# Elektroskate_Teensy_20141227.net
KiCad netlist of a schematic drawn in EAGLE
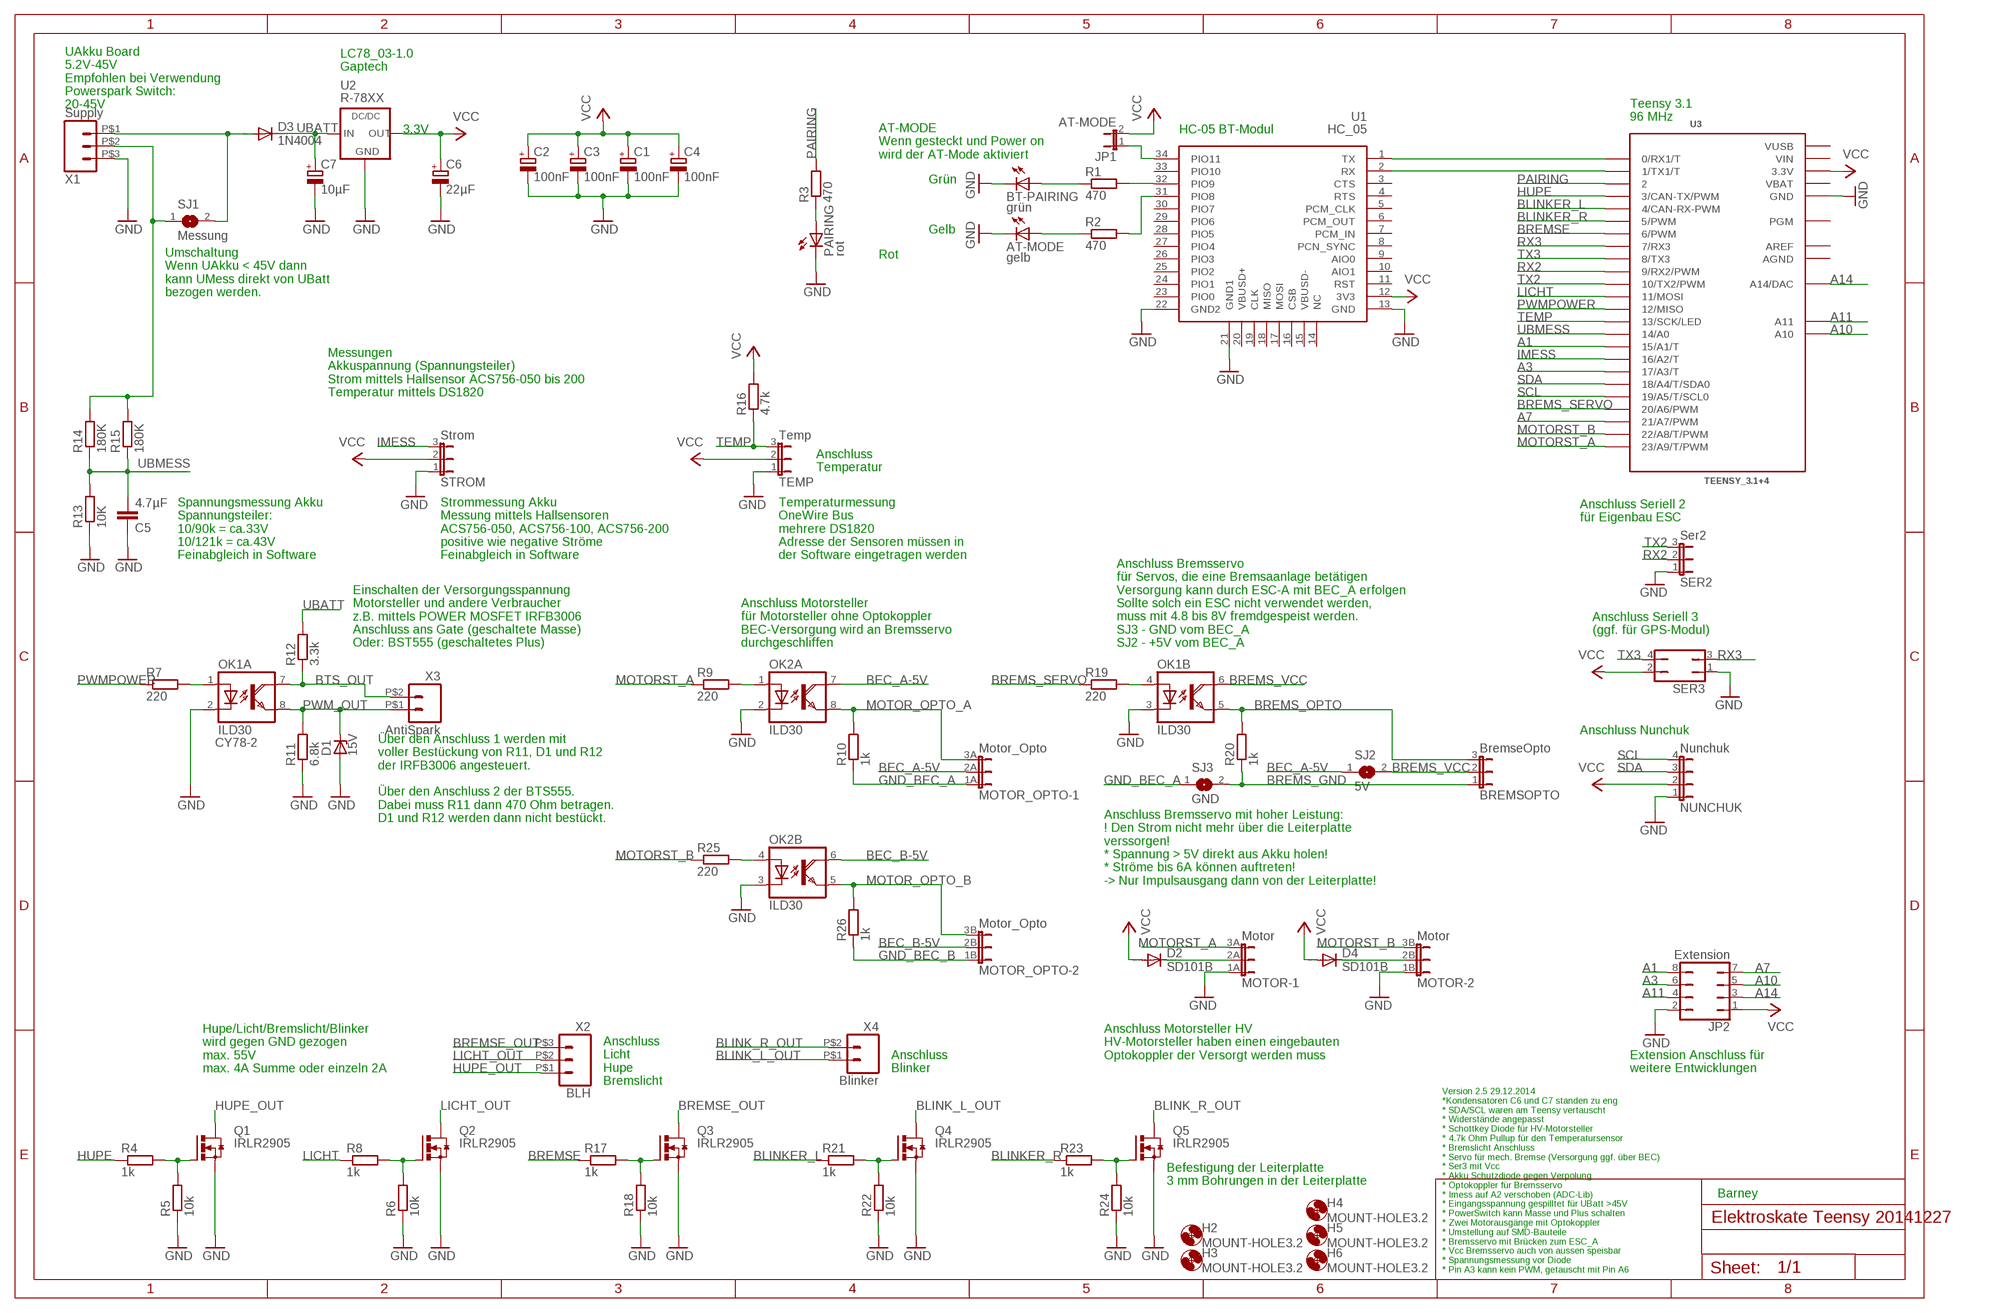
[diagram p0: schematic, sheet 1]

(export (version "E")
  (design (tool "Eeschema 10.0.6"))
  (components
    (comp (ref "AT-MODE")
      (value "gelb")
      (footprint "eagle-import:SML0805")
      (libsource (lib "eagle-import") (part "LEDSML0805"))
    )
    (comp (ref "BREMSOPTO")
      (value "BremseOpto")
      (footprint "eagle-import:JP2")
      (libsource (lib "eagle-import") (part "JP2E"))
    )
    (comp (ref "BT-PAIRING")
      (value "grün")
      (footprint "eagle-import:SML0805")
      (libsource (lib "eagle-import") (part "LEDSML0805"))
    )
    (comp (ref "C1")
      (value "100nF")
      (footprint "eagle-import:B45181A")
      (libsource (lib "eagle-import") (part "CPOL-EUB45181A"))
    )
    (comp (ref "C2")
      (value "100nF")
      (footprint "eagle-import:B45181A")
      (libsource (lib "eagle-import") (part "CPOL-EUB45181A"))
    )
    (comp (ref "C3")
      (value "100nF")
      (footprint "eagle-import:B45181A")
      (libsource (lib "eagle-import") (part "CPOL-EUB45181A"))
    )
    (comp (ref "C4")
      (value "100nF")
      (footprint "eagle-import:B45181A")
      (libsource (lib "eagle-import") (part "CPOL-EUB45181A"))
    )
    (comp (ref "C5")
      (value "4.7µF")
      (footprint "eagle-import:C1206")
      (libsource (lib "eagle-import") (part "C-EUC1206"))
    )
    (comp (ref "C6")
      (value "22µF")
      (footprint "eagle-import:UD-4X5,8_NICHICON")
      (libsource (lib "eagle-import") (part "CPOL-EUUD-4X5,8"))
    )
    (comp (ref "C7")
      (value "10µF")
      (footprint "eagle-import:UD-6,3X5,8_NICHICON")
      (libsource (lib "eagle-import") (part "CPOL-EUUD-6,3X8,8"))
    )
    (comp (ref "D1")
      (value "15V")
      (footprint "eagle-import:DO35Z10")
      (libsource (lib "eagle-import") (part "ZPD"))
    )
    (comp (ref "D2")
      (value "SD101B")
      (footprint "eagle-import:SOD123")
      (libsource (lib "eagle-import") (part "MBR0520LT"))
    )
    (comp (ref "D3")
      (value "1N4004")
      (footprint "eagle-import:DO41-10")
      (libsource (lib "eagle-import") (part "1N4004"))
    )
    (comp (ref "D4")
      (value "SD101B")
      (footprint "eagle-import:SOD123")
      (libsource (lib "eagle-import") (part "MBR0520LT"))
    )
    (comp (ref "H2")
      (value "MOUNT-HOLE3.2")
      (footprint "eagle-import:3,2")
      (libsource (lib "eagle-import") (part "MOUNT-HOLE3.2"))
    )
    (comp (ref "H3")
      (value "MOUNT-HOLE3.2")
      (footprint "eagle-import:3,2")
      (libsource (lib "eagle-import") (part "MOUNT-HOLE3.2"))
    )
    (comp (ref "H4")
      (value "MOUNT-HOLE3.2")
      (footprint "eagle-import:3,2")
      (libsource (lib "eagle-import") (part "MOUNT-HOLE3.2"))
    )
    (comp (ref "H5")
      (value "MOUNT-HOLE3.2")
      (footprint "eagle-import:3,2")
      (libsource (lib "eagle-import") (part "MOUNT-HOLE3.2"))
    )
    (comp (ref "H6")
      (value "MOUNT-HOLE3.2")
      (footprint "eagle-import:3,2")
      (libsource (lib "eagle-import") (part "MOUNT-HOLE3.2"))
    )
    (comp (ref "JP1")
      (value "AT-MODE")
      (footprint "eagle-import:JP1")
      (libsource (lib "eagle-import") (part "JP1E"))
    )
    (comp (ref "JP2")
      (value "Extension")
      (footprint "eagle-import:JP4Q")
      (libsource (lib "eagle-import") (part "JP4Q"))
    )
    (comp (ref "MOTOR")
      (value "Motor")
      (footprint "eagle-import:JP3Q")
      (libsource (lib "eagle-import") (part "JP3QE"))
    )
    (comp (ref "MOTOR_OPTO")
      (value "Motor_Opto")
      (footprint "eagle-import:JP3Q")
      (libsource (lib "eagle-import") (part "JP3QE"))
    )
    (comp (ref "NUNCHUK")
      (value "Nunchuk")
      (footprint "eagle-import:JP4")
      (libsource (lib "eagle-import") (part "JP4E"))
    )
    (comp (ref "OK1")
      (value "ILD30")
      (footprint "eagle-import:DIL08")
      (fields (field (name "MF") "VISHAY/TELEFUNKEN"))
      (libsource (lib "eagle-import") (part "ILD30"))
    )
    (comp (ref "OK2")
      (value "ILD30")
      (footprint "eagle-import:DIL08")
      (fields (field (name "MF") "VISHAY/TELEFUNKEN"))
      (libsource (lib "eagle-import") (part "ILD30"))
    )
    (comp (ref "PAIRING")
      (value "rot")
      (footprint "eagle-import:SML0805")
      (libsource (lib "eagle-import") (part "LEDSML0805"))
    )
    (comp (ref "Q1")
      (value "IRLR2905")
      (footprint "eagle-import:D-PAK_TO252AA")
      (libsource (lib "eagle-import") (part "IRLR2905"))
    )
    (comp (ref "Q2")
      (value "IRLR2905")
      (footprint "eagle-import:D-PAK_TO252AA")
      (libsource (lib "eagle-import") (part "IRLR2905"))
    )
    (comp (ref "Q3")
      (value "IRLR2905")
      (footprint "eagle-import:D-PAK_TO252AA")
      (libsource (lib "eagle-import") (part "IRLR2905"))
    )
    (comp (ref "Q4")
      (value "IRLR2905")
      (footprint "eagle-import:D-PAK_TO252AA")
      (libsource (lib "eagle-import") (part "IRLR2905"))
    )
    (comp (ref "Q5")
      (value "IRLR2905")
      (footprint "eagle-import:D-PAK_TO252AA")
      (libsource (lib "eagle-import") (part "IRLR2905"))
    )
    (comp (ref "R1")
      (value "470")
      (footprint "eagle-import:R1206")
      (libsource (lib "eagle-import") (part "R-EU_R1206"))
    )
    (comp (ref "R2")
      (value "470")
      (footprint "eagle-import:R1206")
      (libsource (lib "eagle-import") (part "R-EU_R1206"))
    )
    (comp (ref "R3")
      (value "470")
      (footprint "eagle-import:R1206")
      (libsource (lib "eagle-import") (part "R-EU_R1206"))
    )
    (comp (ref "R4")
      (value "1k")
      (footprint "eagle-import:R1206")
      (libsource (lib "eagle-import") (part "R-EU_R1206"))
    )
    (comp (ref "R5")
      (value "10k")
      (footprint "eagle-import:R1206")
      (libsource (lib "eagle-import") (part "R-EU_R1206"))
    )
    (comp (ref "R6")
      (value "10k")
      (footprint "eagle-import:R1206")
      (libsource (lib "eagle-import") (part "R-EU_R1206"))
    )
    (comp (ref "R7")
      (value "220")
      (footprint "eagle-import:R1206")
      (libsource (lib "eagle-import") (part "R-EU_R1206"))
    )
    (comp (ref "R8")
      (value "1k")
      (footprint "eagle-import:R1206")
      (libsource (lib "eagle-import") (part "R-EU_R1206"))
    )
    (comp (ref "R9")
      (value "220")
      (footprint "eagle-import:R1206")
      (libsource (lib "eagle-import") (part "R-EU_R1206"))
    )
    (comp (ref "R10")
      (value "1k")
      (footprint "eagle-import:R1206")
      (libsource (lib "eagle-import") (part "R-EU_R1206"))
    )
    (comp (ref "R11")
      (value "6.8k")
      (footprint "eagle-import:R1206")
      (libsource (lib "eagle-import") (part "R-EU_R1206"))
    )
    (comp (ref "R12")
      (value "3.3k")
      (footprint "eagle-import:R1206")
      (libsource (lib "eagle-import") (part "R-EU_R1206"))
    )
    (comp (ref "R13")
      (value "10K")
      (footprint "eagle-import:R1206")
      (libsource (lib "eagle-import") (part "R-EU_R1206"))
    )
    (comp (ref "R14")
      (value "180K")
      (footprint "eagle-import:R1206")
      (libsource (lib "eagle-import") (part "R-EU_R1206"))
    )
    (comp (ref "R15")
      (value "180K")
      (footprint "eagle-import:R1206")
      (libsource (lib "eagle-import") (part "R-EU_R1206"))
    )
    (comp (ref "R16")
      (value "4.7k")
      (footprint "eagle-import:R1206")
      (libsource (lib "eagle-import") (part "R-EU_R1206"))
    )
    (comp (ref "R17")
      (value "1k")
      (footprint "eagle-import:R1206")
      (libsource (lib "eagle-import") (part "R-EU_R1206"))
    )
    (comp (ref "R18")
      (value "10k")
      (footprint "eagle-import:R1206")
      (libsource (lib "eagle-import") (part "R-EU_R1206"))
    )
    (comp (ref "R19")
      (value "220")
      (footprint "eagle-import:R1206")
      (libsource (lib "eagle-import") (part "R-EU_R1206"))
    )
    (comp (ref "R20")
      (value "1k")
      (footprint "eagle-import:R1206")
      (libsource (lib "eagle-import") (part "R-EU_R1206"))
    )
    (comp (ref "R21")
      (value "1k")
      (footprint "eagle-import:R1206")
      (libsource (lib "eagle-import") (part "R-EU_R1206"))
    )
    (comp (ref "R22")
      (value "10k")
      (footprint "eagle-import:R1206")
      (libsource (lib "eagle-import") (part "R-EU_R1206"))
    )
    (comp (ref "R23")
      (value "1k")
      (footprint "eagle-import:R1206")
      (libsource (lib "eagle-import") (part "R-EU_R1206"))
    )
    (comp (ref "R24")
      (value "10k")
      (footprint "eagle-import:R1206")
      (libsource (lib "eagle-import") (part "R-EU_R1206"))
    )
    (comp (ref "R25")
      (value "220")
      (footprint "eagle-import:R1206")
      (libsource (lib "eagle-import") (part "R-EU_R1206"))
    )
    (comp (ref "R26")
      (value "1k")
      (footprint "eagle-import:R1206")
      (libsource (lib "eagle-import") (part "R-EU_R1206"))
    )
    (comp (ref "SER2")
      (value "Ser2")
      (footprint "eagle-import:JP2")
      (libsource (lib "eagle-import") (part "JP2E"))
    )
    (comp (ref "SER3")
      (value "JP2Q")
      (footprint "eagle-import:JP2Q")
      (libsource (lib "eagle-import") (part "JP2Q"))
    )
    (comp (ref "SJ1")
      (value "Messung")
      (footprint "eagle-import:SJ")
      (libsource (lib "eagle-import") (part "SJ"))
    )
    (comp (ref "SJ2") (value "5V") (footprint "eagle-import:SJ") (libsource (lib "eagle-import") (part "SJ")))
    (comp (ref "SJ3")
      (value "GND")
      (footprint "eagle-import:SJ")
      (libsource (lib "eagle-import") (part "SJ"))
    )
    (comp (ref "STROM")
      (value "Strom")
      (footprint "eagle-import:JP2")
      (libsource (lib "eagle-import") (part "JP2E"))
    )
    (comp (ref "TEMP")
      (value "Temp")
      (footprint "eagle-import:JP2")
      (libsource (lib "eagle-import") (part "JP2E"))
    )
    (comp (ref "U1")
      (value "HC_05")
      (footprint "eagle-import:BLUETOOTH_SMD")
      (libsource (lib "eagle-import") (part "HC_05"))
    )
    (comp (ref "U2")
      (value "R-78XX")
      (footprint "eagle-import:R-78XX")
      (fields (field (name "SPANNUNG") "3.3V"))
      (libsource (lib "eagle-import") (part "R-78XX"))
    )
    (comp (ref "U3")
      (value "TEENSY_3.1+4")
      (footprint "eagle-import:TEENSY_3.1+4")
      (libsource (lib "eagle-import") (part "TEENSY_3.1+4"))
    )
    (comp (ref "X1")
      (value "Supply")
      (footprint "eagle-import:03W")
      (libsource (lib "eagle-import") (part "PSS254_3GEWINKELT"))
    )
    (comp (ref "X2")
      (value "BLH")
      (footprint "eagle-import:03W")
      (libsource (lib "eagle-import") (part "PSS254_3GEWINKELT"))
    )
    (comp (ref "X3")
      (value "AntiSpark")
      (footprint "eagle-import:02W")
      (libsource (lib "eagle-import") (part "PSS254_2GEWINKELT"))
    )
    (comp (ref "X4")
      (value "Blinker")
      (footprint "eagle-import:02W")
      (libsource (lib "eagle-import") (part "PSS254_2GEWINKELT"))
    )
  )
  (nets
    (net (code "1") (name "/A1") (class "Default")
      (node (ref "JP2") (pin "8") (pinfunction "8_8") (pintype "passive"))
      (node (ref "U3") (pin "15/A1") (pinfunction "15/A1/T_15/A1") (pintype "bidirectional"))
    )
    (net (code "2") (name "/A3") (class "Default")
      (node (ref "JP2") (pin "6") (pinfunction "6_6") (pintype "passive"))
      (node (ref "U3") (pin "17/A3") (pinfunction "17/A3/T_17/A3") (pintype "bidirectional"))
    )
    (net (code "3") (name "/A7") (class "Default")
      (node (ref "JP2") (pin "7") (pinfunction "7_7") (pintype "passive"))
      (node (ref "U3") (pin "21/A7") (pinfunction "21/A7/PWM_21/A7") (pintype "bidirectional"))
    )
    (net (code "4") (name "/A10") (class "Default")
      (node (ref "JP2") (pin "5") (pinfunction "5_5") (pintype "passive"))
      (node (ref "U3") (pin "A10") (pinfunction "A10_A10") (pintype "bidirectional"))
    )
    (net (code "5") (name "/A11") (class "Default")
      (node (ref "JP2") (pin "4") (pinfunction "4_4") (pintype "passive"))
      (node (ref "U3") (pin "A11") (pinfunction "A11_A11") (pintype "bidirectional"))
    )
    (net (code "6") (name "/A14") (class "Default")
      (node (ref "JP2") (pin "3") (pinfunction "3_3") (pintype "passive"))
      (node (ref "U3") (pin "A14") (pinfunction "A14/DAC_A14") (pintype "bidirectional"))
    )
    (net (code "7") (name "/AGND") (class "Default")
      (node (ref "U3") (pin "AGND") (pinfunction "AGND_AGND") (pintype "power_in"))
    )
    (net (code "8") (name "/AREF") (class "Default")
      (node (ref "U3") (pin "AREF") (pinfunction "AREF_AREF") (pintype "power_in"))
    )
    (net (code "9") (name "/BEC_A-5V") (class "Default")
      (node (ref "MOTOR_OPTO") (pin "2A") (pinfunction "2_2A") (pintype "passive"))
      (node (ref "OK2") (pin "7") (pinfunction "COL_7") (pintype "passive"))
      (node (ref "SJ2") (pin "1") (pinfunction "1_1") (pintype "passive"))
    )
    (net (code "10") (name "/BEC_B-5V") (class "Default")
      (node (ref "MOTOR_OPTO") (pin "2B") (pinfunction "2_2B") (pintype "passive"))
      (node (ref "OK2") (pin "6") (pinfunction "COL_6") (pintype "passive"))
    )
    (net (code "11") (name "/BLINKER_L") (class "Default")
      (node (ref "R21") (pin "1") (pinfunction "1_1") (pintype "passive"))
      (node (ref "U3") (pin "4") (pinfunction "4/CAN-RX-PWM_4") (pintype "bidirectional"))
    )
    (net (code "12") (name "/BLINKER_R") (class "Default")
      (node (ref "R23") (pin "1") (pinfunction "1_1") (pintype "passive"))
      (node (ref "U3") (pin "5") (pinfunction "5/PWM_5") (pintype "bidirectional"))
    )
    (net (code "13") (name "/BLINK_L_OUT") (class "Default")
      (node (ref "Q4") (pin "4") (pinfunction "D_4") (pintype "passive"))
      (node (ref "X4") (pin "P$1") (pinfunction "1_P$1") (pintype "passive"))
    )
    (net (code "14") (name "/BLINK_R_OUT") (class "Default")
      (node (ref "Q5") (pin "4") (pinfunction "D_4") (pintype "passive"))
      (node (ref "X4") (pin "P$2") (pinfunction "2_P$2") (pintype "passive"))
    )
    (net (code "15") (name "/BREMSE") (class "Default")
      (node (ref "R17") (pin "1") (pinfunction "1_1") (pintype "passive"))
      (node (ref "U3") (pin "6") (pinfunction "6/PWM_6") (pintype "bidirectional"))
    )
    (net (code "16") (name "/BREMSE_OUT") (class "Default")
      (node (ref "Q3") (pin "4") (pinfunction "D_4") (pintype "passive"))
      (node (ref "X2") (pin "P$3") (pinfunction "3_P$3") (pintype "passive"))
    )
    (net (code "17") (name "/BREMS_GND") (class "Default")
      (node (ref "BREMSOPTO") (pin "1") (pinfunction "1_1") (pintype "passive"))
      (node (ref "R20") (pin "1") (pinfunction "1_1") (pintype "passive"))
      (node (ref "SJ3") (pin "2") (pinfunction "2_2") (pintype "passive"))
    )
    (net (code "18") (name "/BREMS_OPTO") (class "Default")
      (node (ref "BREMSOPTO") (pin "3") (pinfunction "3_3") (pintype "passive"))
      (node (ref "OK1") (pin "5") (pinfunction "EMI_5") (pintype "passive"))
      (node (ref "R20") (pin "2") (pinfunction "2_2") (pintype "passive"))
    )
    (net (code "19") (name "/BREMS_SERVO") (class "Default")
      (node (ref "R19") (pin "1") (pinfunction "1_1") (pintype "passive"))
      (node (ref "U3") (pin "20/A6") (pinfunction "20/A6/PWM_20/A6") (pintype "bidirectional"))
    )
    (net (code "20") (name "/BREMS_VCC") (class "Default")
      (node (ref "BREMSOPTO") (pin "2") (pinfunction "2_2") (pintype "passive"))
      (node (ref "OK1") (pin "6") (pinfunction "COL_6") (pintype "passive"))
      (node (ref "SJ2") (pin "2") (pinfunction "2_2") (pintype "passive"))
    )
    (net (code "21") (name "/BTS_OUT") (class "Default")
      (node (ref "OK1") (pin "7") (pinfunction "COL_7") (pintype "passive"))
      (node (ref "R12") (pin "1") (pinfunction "1_1") (pintype "passive"))
      (node (ref "X3") (pin "P$2") (pinfunction "2_P$2") (pintype "passive"))
    )
    (net (code "22") (name "/GND_BEC_A") (class "Default")
      (node (ref "MOTOR_OPTO") (pin "1A") (pinfunction "1_1A") (pintype "passive"))
      (node (ref "R10") (pin "1") (pinfunction "1_1") (pintype "passive"))
      (node (ref "SJ3") (pin "1") (pinfunction "1_1") (pintype "passive"))
    )
    (net (code "23") (name "/GND_BEC_B") (class "Default")
      (node (ref "MOTOR_OPTO") (pin "1B") (pinfunction "1_1B") (pintype "passive"))
      (node (ref "R26") (pin "1") (pinfunction "1_1") (pintype "passive"))
    )
    (net (code "24") (name "/HUPE") (class "Default")
      (node (ref "R4") (pin "1") (pinfunction "1_1") (pintype "passive"))
      (node (ref "U3") (pin "3") (pinfunction "3/CAN-TX/PWM_3") (pintype "bidirectional"))
    )
    (net (code "25") (name "/HUPE_OUT") (class "Default")
      (node (ref "Q1") (pin "4") (pinfunction "D_4") (pintype "passive"))
      (node (ref "X2") (pin "P$1") (pinfunction "1_P$1") (pintype "passive"))
    )
    (net (code "26") (name "/IMESS") (class "Default")
      (node (ref "STROM") (pin "3") (pinfunction "3_3") (pintype "passive"))
      (node (ref "U3") (pin "16/A2") (pinfunction "16/A2/T_16/A2") (pintype "bidirectional"))
    )
    (net (code "27") (name "/LICHT") (class "Default")
      (node (ref "R8") (pin "1") (pinfunction "1_1") (pintype "passive"))
      (node (ref "U3") (pin "11") (pinfunction "11/MOSI_11") (pintype "bidirectional"))
    )
    (net (code "28") (name "/LICHT_OUT") (class "Default")
      (node (ref "Q2") (pin "4") (pinfunction "D_4") (pintype "passive"))
      (node (ref "X2") (pin "P$2") (pinfunction "2_P$2") (pintype "passive"))
    )
    (net (code "29") (name "/MOTORST_A") (class "Default")
      (node (ref "MOTOR") (pin "3A") (pinfunction "3_3A") (pintype "passive"))
      (node (ref "R9") (pin "1") (pinfunction "1_1") (pintype "passive"))
      (node (ref "U3") (pin "23/A9") (pinfunction "23/A9/T/PWM_23/A9") (pintype "bidirectional"))
    )
    (net (code "30") (name "/MOTORST_B") (class "Default")
      (node (ref "MOTOR") (pin "3B") (pinfunction "3_3B") (pintype "passive"))
      (node (ref "R25") (pin "1") (pinfunction "1_1") (pintype "passive"))
      (node (ref "U3") (pin "22/A8") (pinfunction "22/A8/T/PWM_22/A8") (pintype "bidirectional"))
    )
    (net (code "31") (name "/MOTOR_OPTO_A") (class "Default")
      (node (ref "MOTOR_OPTO") (pin "3A") (pinfunction "3_3A") (pintype "passive"))
      (node (ref "OK2") (pin "8") (pinfunction "EMI_8") (pintype "passive"))
      (node (ref "R10") (pin "2") (pinfunction "2_2") (pintype "passive"))
    )
    (net (code "32") (name "/MOTOR_OPTO_B") (class "Default")
      (node (ref "MOTOR_OPTO") (pin "3B") (pinfunction "3_3B") (pintype "passive"))
      (node (ref "OK2") (pin "5") (pinfunction "EMI_5") (pintype "passive"))
      (node (ref "R26") (pin "2") (pinfunction "2_2") (pintype "passive"))
    )
    (net (code "33") (name "/PAIRING") (class "Default")
      (node (ref "R3") (pin "2") (pinfunction "2_2") (pintype "passive"))
      (node (ref "U3") (pin "2") (pinfunction "2_2") (pintype "bidirectional"))
    )
    (net (code "34") (name "/PWMPOWER") (class "Default")
      (node (ref "R7") (pin "1") (pinfunction "1_1") (pintype "passive"))
      (node (ref "U3") (pin "12") (pinfunction "12/MISO_12") (pintype "bidirectional"))
    )
    (net (code "35") (name "/PWM_OUT") (class "Default")
      (node (ref "D1") (pin "C") (pinfunction "C_C") (pintype "passive"))
      (node (ref "OK1") (pin "8") (pinfunction "EMI_8") (pintype "passive"))
      (node (ref "R11") (pin "2") (pinfunction "2_2") (pintype "passive"))
      (node (ref "X3") (pin "P$1") (pinfunction "1_P$1") (pintype "passive"))
    )
    (net (code "36") (name "/RX2") (class "Default")
      (node (ref "SER2") (pin "2") (pinfunction "2_2") (pintype "passive"))
      (node (ref "U3") (pin "9") (pinfunction "9/RX2/PWM_9") (pintype "bidirectional"))
    )
    (net (code "37") (name "/RX3") (class "Default")
      (node (ref "SER3") (pin "3") (pinfunction "3_3") (pintype "passive"))
      (node (ref "U3") (pin "7") (pinfunction "7/RX3_7") (pintype "bidirectional"))
    )
    (net (code "38") (name "/SCL") (class "Default")
      (node (ref "NUNCHUK") (pin "4") (pinfunction "4_4") (pintype "passive"))
      (node (ref "U3") (pin "19/A5") (pinfunction "19/A5/T/SCL0_19/A5") (pintype "bidirectional"))
    )
    (net (code "39") (name "/SDA") (class "Default")
      (node (ref "NUNCHUK") (pin "3") (pinfunction "3_3") (pintype "passive"))
      (node (ref "U3") (pin "18/A4") (pinfunction "18/A4/T/SDA0_18/A4") (pintype "bidirectional"))
    )
    (net (code "40") (name "/TEMP") (class "Default")
      (node (ref "R16") (pin "1") (pinfunction "1_1") (pintype "passive"))
      (node (ref "TEMP") (pin "3") (pinfunction "3_3") (pintype "passive"))
      (node (ref "U3") (pin "13") (pinfunction "13/SCK/LED_13") (pintype "bidirectional"))
    )
    (net (code "41") (name "/TX2") (class "Default")
      (node (ref "SER2") (pin "3") (pinfunction "3_3") (pintype "passive"))
      (node (ref "U3") (pin "10") (pinfunction "10/TX2/PWM_10") (pintype "bidirectional"))
    )
    (net (code "42") (name "/TX3") (class "Default")
      (node (ref "SER3") (pin "4") (pinfunction "4_4") (pintype "passive"))
      (node (ref "U3") (pin "8") (pinfunction "8/TX3_8") (pintype "bidirectional"))
    )
    (net (code "43") (name "/UBATT") (class "Default")
      (node (ref "C7") (pin "+") (pinfunction "+_+") (pintype "passive"))
      (node (ref "D3") (pin "C") (pinfunction "C_C") (pintype "passive"))
      (node (ref "R12") (pin "2") (pinfunction "2_2") (pintype "passive"))
      (node (ref "U2") (pin "1") (pinfunction "IN_1") (pintype "input"))
    )
    (net (code "44") (name "/UBMESS") (class "Default")
      (node (ref "C5") (pin "2") (pinfunction "2_2") (pintype "passive"))
      (node (ref "R13") (pin "2") (pinfunction "2_2") (pintype "passive"))
      (node (ref "R14") (pin "1") (pinfunction "1_1") (pintype "passive"))
      (node (ref "R15") (pin "1") (pinfunction "1_1") (pintype "passive"))
      (node (ref "U3") (pin "14/A0") (pinfunction "14/A0_14/A0") (pintype "bidirectional"))
    )
    (net (code "45") (name "/VBAT") (class "Default")
      (node (ref "U3") (pin "VBAT") (pinfunction "VBAT_VBAT") (pintype "power_in"))
    )
    (net (code "46") (name "/VIN") (class "Default")
      (node (ref "U3") (pin "VIN") (pinfunction "VIN_VIN") (pintype "power_in"))
    )
    (net (code "47") (name "/VUSB") (class "Default")
      (node (ref "U3") (pin "VUSB") (pinfunction "VUSB_VUSB") (pintype "power_in"))
    )
    (net (code "48") (name "GND") (class "Default")
      (node (ref "AT-MODE") (pin "C") (pinfunction "C_C") (pintype "passive"))
      (node (ref "BT-PAIRING") (pin "C") (pinfunction "C_C") (pintype "passive"))
      (node (ref "C1") (pin "-") (pinfunction "-_-") (pintype "passive"))
      (node (ref "C2") (pin "-") (pinfunction "-_-") (pintype "passive"))
      (node (ref "C3") (pin "-") (pinfunction "-_-") (pintype "passive"))
      (node (ref "C4") (pin "-") (pinfunction "-_-") (pintype "passive"))
      (node (ref "C5") (pin "1") (pinfunction "1_1") (pintype "passive"))
      (node (ref "C6") (pin "-") (pinfunction "-_-") (pintype "passive"))
      (node (ref "C7") (pin "-") (pinfunction "-_-") (pintype "passive"))
      (node (ref "D1") (pin "A") (pinfunction "A_A") (pintype "passive"))
      (node (ref "JP2") (pin "2") (pinfunction "2_2") (pintype "passive"))
      (node (ref "MOTOR") (pin "1A") (pinfunction "1_1A") (pintype "passive"))
      (node (ref "MOTOR") (pin "1B") (pinfunction "1_1B") (pintype "passive"))
      (node (ref "NUNCHUK") (pin "1") (pinfunction "1_1") (pintype "passive"))
      (node (ref "OK1") (pin "2") (pinfunction "C_2") (pintype "passive"))
      (node (ref "OK1") (pin "3") (pinfunction "C_3") (pintype "passive"))
      (node (ref "OK2") (pin "2") (pinfunction "C_2") (pintype "passive"))
      (node (ref "OK2") (pin "3") (pinfunction "C_3") (pintype "passive"))
      (node (ref "PAIRING") (pin "C") (pinfunction "C_C") (pintype "passive"))
      (node (ref "Q1") (pin "3") (pinfunction "S_3") (pintype "passive"))
      (node (ref "Q2") (pin "3") (pinfunction "S_3") (pintype "passive"))
      (node (ref "Q3") (pin "3") (pinfunction "S_3") (pintype "passive"))
      (node (ref "Q4") (pin "3") (pinfunction "S_3") (pintype "passive"))
      (node (ref "Q5") (pin "3") (pinfunction "S_3") (pintype "passive"))
      (node (ref "R11") (pin "1") (pinfunction "1_1") (pintype "passive"))
      (node (ref "R13") (pin "1") (pinfunction "1_1") (pintype "passive"))
      (node (ref "R18") (pin "1") (pinfunction "1_1") (pintype "passive"))
      (node (ref "R22") (pin "1") (pinfunction "1_1") (pintype "passive"))
      (node (ref "R24") (pin "1") (pinfunction "1_1") (pintype "passive"))
      (node (ref "R5") (pin "1") (pinfunction "1_1") (pintype "passive"))
      (node (ref "R6") (pin "1") (pinfunction "1_1") (pintype "passive"))
      (node (ref "SER2") (pin "1") (pinfunction "1_1") (pintype "passive"))
      (node (ref "SER3") (pin "1") (pinfunction "1_1") (pintype "passive"))
      (node (ref "STROM") (pin "1") (pinfunction "1_1") (pintype "passive"))
      (node (ref "TEMP") (pin "1") (pinfunction "1_1") (pintype "passive"))
      (node (ref "U1") (pin "13") (pinfunction "GND_13") (pintype "bidirectional"))
      (node (ref "U1") (pin "21") (pinfunction "GND1_21") (pintype "bidirectional"))
      (node (ref "U1") (pin "22") (pinfunction "GND2_22") (pintype "bidirectional"))
      (node (ref "U2") (pin "2") (pinfunction "GND_2") (pintype "input"))
      (node (ref "U3") (pin "GND") (pinfunction "GND_GND") (pintype "power_in"))
      (node (ref "U3") (pin "GND1") (pinfunction "GND_GND1") (pintype "power_in"))
      (node (ref "X1") (pin "P$3") (pinfunction "3_P$3") (pintype "passive"))
    )
    (net (code "49") (name "Net-(AT-MODE-PadA)") (class "Default")
      (node (ref "AT-MODE") (pin "A") (pinfunction "A_A") (pintype "passive"))
      (node (ref "R2") (pin "1") (pinfunction "1_1") (pintype "passive"))
    )
    (net (code "50") (name "Net-(BT-PAIRING-PadA)") (class "Default")
      (node (ref "BT-PAIRING") (pin "A") (pinfunction "A_A") (pintype "passive"))
      (node (ref "R1") (pin "1") (pinfunction "1_1") (pintype "passive"))
    )
    (net (code "51") (name "Net-(MOTORA-2)") (class "Default")
      (node (ref "D2") (pin "C") (pinfunction "C_C") (pintype "passive"))
      (node (ref "MOTOR") (pin "2A") (pinfunction "2_2A") (pintype "passive"))
    )
    (net (code "52") (name "Net-(MOTORB-2)") (class "Default")
      (node (ref "D4") (pin "C") (pinfunction "C_C") (pintype "passive"))
      (node (ref "MOTOR") (pin "2B") (pinfunction "2_2B") (pintype "passive"))
    )
    (net (code "53") (name "Net-(OK1A-A)") (class "Default")
      (node (ref "OK1") (pin "1") (pinfunction "A_1") (pintype "passive"))
      (node (ref "R7") (pin "2") (pinfunction "2_2") (pintype "passive"))
    )
    (net (code "54") (name "Net-(OK1B-A)") (class "Default")
      (node (ref "OK1") (pin "4") (pinfunction "A_4") (pintype "passive"))
      (node (ref "R19") (pin "2") (pinfunction "2_2") (pintype "passive"))
    )
    (net (code "55") (name "Net-(OK2A-A)") (class "Default")
      (node (ref "OK2") (pin "1") (pinfunction "A_1") (pintype "passive"))
      (node (ref "R9") (pin "2") (pinfunction "2_2") (pintype "passive"))
    )
    (net (code "56") (name "Net-(OK2B-A)") (class "Default")
      (node (ref "OK2") (pin "4") (pinfunction "A_4") (pintype "passive"))
      (node (ref "R25") (pin "2") (pinfunction "2_2") (pintype "passive"))
    )
    (net (code "57") (name "Net-(PAIRING-PadA)") (class "Default")
      (node (ref "PAIRING") (pin "A") (pinfunction "A_A") (pintype "passive"))
      (node (ref "R3") (pin "1") (pinfunction "1_1") (pintype "passive"))
    )
    (net (code "58") (name "Net-(Q1-G)") (class "Default")
      (node (ref "Q1") (pin "1") (pinfunction "G_1") (pintype "passive"))
      (node (ref "R4") (pin "2") (pinfunction "2_2") (pintype "passive"))
      (node (ref "R5") (pin "2") (pinfunction "2_2") (pintype "passive"))
    )
    (net (code "59") (name "Net-(Q2-G)") (class "Default")
      (node (ref "Q2") (pin "1") (pinfunction "G_1") (pintype "passive"))
      (node (ref "R6") (pin "2") (pinfunction "2_2") (pintype "passive"))
      (node (ref "R8") (pin "2") (pinfunction "2_2") (pintype "passive"))
    )
    (net (code "60") (name "Net-(Q3-G)") (class "Default")
      (node (ref "Q3") (pin "1") (pinfunction "G_1") (pintype "passive"))
      (node (ref "R17") (pin "2") (pinfunction "2_2") (pintype "passive"))
      (node (ref "R18") (pin "2") (pinfunction "2_2") (pintype "passive"))
    )
    (net (code "61") (name "Net-(Q4-G)") (class "Default")
      (node (ref "Q4") (pin "1") (pinfunction "G_1") (pintype "passive"))
      (node (ref "R21") (pin "2") (pinfunction "2_2") (pintype "passive"))
      (node (ref "R22") (pin "2") (pinfunction "2_2") (pintype "passive"))
    )
    (net (code "62") (name "Net-(Q5-G)") (class "Default")
      (node (ref "Q5") (pin "1") (pinfunction "G_1") (pintype "passive"))
      (node (ref "R23") (pin "2") (pinfunction "2_2") (pintype "passive"))
      (node (ref "R24") (pin "2") (pinfunction "2_2") (pintype "passive"))
    )
    (net (code "63") (name "Net-(U1-PIO8)") (class "Default")
      (node (ref "R2") (pin "2") (pinfunction "2_2") (pintype "passive"))
      (node (ref "U1") (pin "31") (pinfunction "PIO8_31") (pintype "bidirectional"))
    )
    (net (code "64") (name "Net-(U1-PIO9)") (class "Default")
      (node (ref "R1") (pin "2") (pinfunction "2_2") (pintype "passive"))
      (node (ref "U1") (pin "32") (pinfunction "PIO9_32") (pintype "bidirectional"))
    )
    (net (code "65") (name "Net-(U1-PIO11)") (class "Default")
      (node (ref "JP1") (pin "1") (pinfunction "1_1") (pintype "passive"))
      (node (ref "U1") (pin "34") (pinfunction "PIO11_34") (pintype "bidirectional"))
    )
    (net (code "66") (name "Net-(U1-RX)") (class "Default")
      (node (ref "U1") (pin "2") (pinfunction "RX_2") (pintype "bidirectional"))
      (node (ref "U3") (pin "1") (pinfunction "1/TX1/T_1") (pintype "bidirectional"))
    )
    (net (code "67") (name "Net-(U1-TX)") (class "Default")
      (node (ref "U1") (pin "1") (pinfunction "TX_1") (pintype "bidirectional"))
      (node (ref "U3") (pin "0") (pinfunction "0/RX1/T_0") (pintype "bidirectional"))
    )
    (net (code "68") (name "Net-(X1-1)") (class "Default")
      (node (ref "D3") (pin "A") (pinfunction "A_A") (pintype "passive"))
      (node (ref "SJ1") (pin "2") (pinfunction "2_2") (pintype "passive"))
      (node (ref "X1") (pin "P$1") (pinfunction "1_P$1") (pintype "passive"))
    )
    (net (code "69") (name "Net-(X1-2)") (class "Default")
      (node (ref "R14") (pin "2") (pinfunction "2_2") (pintype "passive"))
      (node (ref "R15") (pin "2") (pinfunction "2_2") (pintype "passive"))
      (node (ref "SJ1") (pin "1") (pinfunction "1_1") (pintype "passive"))
      (node (ref "X1") (pin "P$2") (pinfunction "2_P$2") (pintype "passive"))
    )
    (net (code "70") (name "VCC") (class "Default")
      (node (ref "C1") (pin "+") (pinfunction "+_+") (pintype "passive"))
      (node (ref "C2") (pin "+") (pinfunction "+_+") (pintype "passive"))
      (node (ref "C3") (pin "+") (pinfunction "+_+") (pintype "passive"))
      (node (ref "C4") (pin "+") (pinfunction "+_+") (pintype "passive"))
      (node (ref "C6") (pin "+") (pinfunction "+_+") (pintype "passive"))
      (node (ref "D2") (pin "A") (pinfunction "A_A") (pintype "passive"))
      (node (ref "D4") (pin "A") (pinfunction "A_A") (pintype "passive"))
      (node (ref "JP1") (pin "2") (pinfunction "2_2") (pintype "passive"))
      (node (ref "JP2") (pin "1") (pinfunction "1_1") (pintype "passive"))
      (node (ref "NUNCHUK") (pin "2") (pinfunction "2_2") (pintype "passive"))
      (node (ref "R16") (pin "2") (pinfunction "2_2") (pintype "passive"))
      (node (ref "SER3") (pin "2") (pinfunction "2_2") (pintype "passive"))
      (node (ref "STROM") (pin "2") (pinfunction "2_2") (pintype "passive"))
      (node (ref "TEMP") (pin "2") (pinfunction "2_2") (pintype "passive"))
      (node (ref "U1") (pin "12") (pinfunction "3V3_12") (pintype "bidirectional"))
      (node (ref "U2") (pin "3") (pinfunction "OUT_3") (pintype "passive"))
      (node (ref "U3") (pin "3.3V") (pinfunction "3.3V_3.3V") (pintype "power_in"))
      (node (ref "U3") (pin "3.3V1") (pinfunction "3.3V_3.3V1") (pintype "power_in"))
    )
    (net (code "71") (name "unconnected-(U1-AIO0-Pad9)") (class "Default")
      (node (ref "U1") (pin "9") (pinfunction "AIO0_9") (pintype "bidirectional"))
    )
    (net (code "72") (name "unconnected-(U1-AIO1-Pad10)") (class "Default")
      (node (ref "U1") (pin "10") (pinfunction "AIO1_10") (pintype "bidirectional"))
    )
    (net (code "73") (name "unconnected-(U1-CLK-Pad19)") (class "Default")
      (node (ref "U1") (pin "19") (pinfunction "CLK_19") (pintype "bidirectional"))
    )
    (net (code "74") (name "unconnected-(U1-CSB-Pad16)") (class "Default")
      (node (ref "U1") (pin "16") (pinfunction "CSB_16") (pintype "bidirectional"))
    )
    (net (code "75") (name "unconnected-(U1-CTS-Pad3)") (class "Default")
      (node (ref "U1") (pin "3") (pinfunction "CTS_3") (pintype "bidirectional"))
    )
    (net (code "76") (name "unconnected-(U1-MISO-Pad18)") (class "Default")
      (node (ref "U1") (pin "18") (pinfunction "MISO_18") (pintype "bidirectional"))
    )
    (net (code "77") (name "unconnected-(U1-MOSI-Pad17)") (class "Default")
      (node (ref "U1") (pin "17") (pinfunction "MOSI_17") (pintype "bidirectional"))
    )
    (net (code "78") (name "unconnected-(U1-NC-Pad14)") (class "Default")
      (node (ref "U1") (pin "14") (pinfunction "NC_14") (pintype "bidirectional"))
    )
    (net (code "79") (name "unconnected-(U1-PCM_CLK-Pad5)") (class "Default")
      (node (ref "U1") (pin "5") (pinfunction "PCM_CLK_5") (pintype "bidirectional"))
    )
    (net (code "80") (name "unconnected-(U1-PCM_IN-Pad7)") (class "Default")
      (node (ref "U1") (pin "7") (pinfunction "PCM_IN_7") (pintype "bidirectional"))
    )
    (net (code "81") (name "unconnected-(U1-PCM_OUT-Pad6)") (class "Default")
      (node (ref "U1") (pin "6") (pinfunction "PCM_OUT_6") (pintype "bidirectional"))
    )
    (net (code "82") (name "unconnected-(U1-PCN_SYNC-Pad8)") (class "Default")
      (node (ref "U1") (pin "8") (pinfunction "PCN_SYNC_8") (pintype "bidirectional"))
    )
    (net (code "83") (name "unconnected-(U1-PIO0-Pad23)") (class "Default")
      (node (ref "U1") (pin "23") (pinfunction "PIO0_23") (pintype "bidirectional"))
    )
    (net (code "84") (name "unconnected-(U1-PIO1-Pad24)") (class "Default")
      (node (ref "U1") (pin "24") (pinfunction "PIO1_24") (pintype "bidirectional"))
    )
    (net (code "85") (name "unconnected-(U1-PIO2-Pad25)") (class "Default")
      (node (ref "U1") (pin "25") (pinfunction "PIO2_25") (pintype "bidirectional"))
    )
    (net (code "86") (name "unconnected-(U1-PIO3-Pad26)") (class "Default")
      (node (ref "U1") (pin "26") (pinfunction "PIO3_26") (pintype "bidirectional"))
    )
    (net (code "87") (name "unconnected-(U1-PIO4-Pad27)") (class "Default")
      (node (ref "U1") (pin "27") (pinfunction "PIO4_27") (pintype "bidirectional"))
    )
    (net (code "88") (name "unconnected-(U1-PIO5-Pad28)") (class "Default")
      (node (ref "U1") (pin "28") (pinfunction "PIO5_28") (pintype "bidirectional"))
    )
    (net (code "89") (name "unconnected-(U1-PIO6-Pad29)") (class "Default")
      (node (ref "U1") (pin "29") (pinfunction "PIO6_29") (pintype "bidirectional"))
    )
    (net (code "90") (name "unconnected-(U1-PIO7-Pad30)") (class "Default")
      (node (ref "U1") (pin "30") (pinfunction "PIO7_30") (pintype "bidirectional"))
    )
    (net (code "91") (name "unconnected-(U1-PIO10-Pad33)") (class "Default")
      (node (ref "U1") (pin "33") (pinfunction "PIO10_33") (pintype "bidirectional"))
    )
    (net (code "92") (name "unconnected-(U1-RST-Pad11)") (class "Default")
      (node (ref "U1") (pin "11") (pinfunction "RST_11") (pintype "bidirectional"))
    )
    (net (code "93") (name "unconnected-(U1-RTS-Pad4)") (class "Default")
      (node (ref "U1") (pin "4") (pinfunction "RTS_4") (pintype "bidirectional"))
    )
    (net (code "94") (name "unconnected-(U1-VBUSD+-Pad20)") (class "Default")
      (node (ref "U1") (pin "20") (pinfunction "VBUSD+_20") (pintype "bidirectional"))
    )
    (net (code "95") (name "unconnected-(U1-VBUSD--Pad15)") (class "Default")
      (node (ref "U1") (pin "15") (pinfunction "VBUSD-_15") (pintype "bidirectional"))
    )
    (net (code "96") (name "unconnected-(U3-PadPGM)") (class "Default")
      (node (ref "U3") (pin "PGM") (pinfunction "PGM_PGM") (pintype "bidirectional"))
    )
  )
)
